# mini_system.net
KiCad netlist of a schematic drawn in Altium Designer
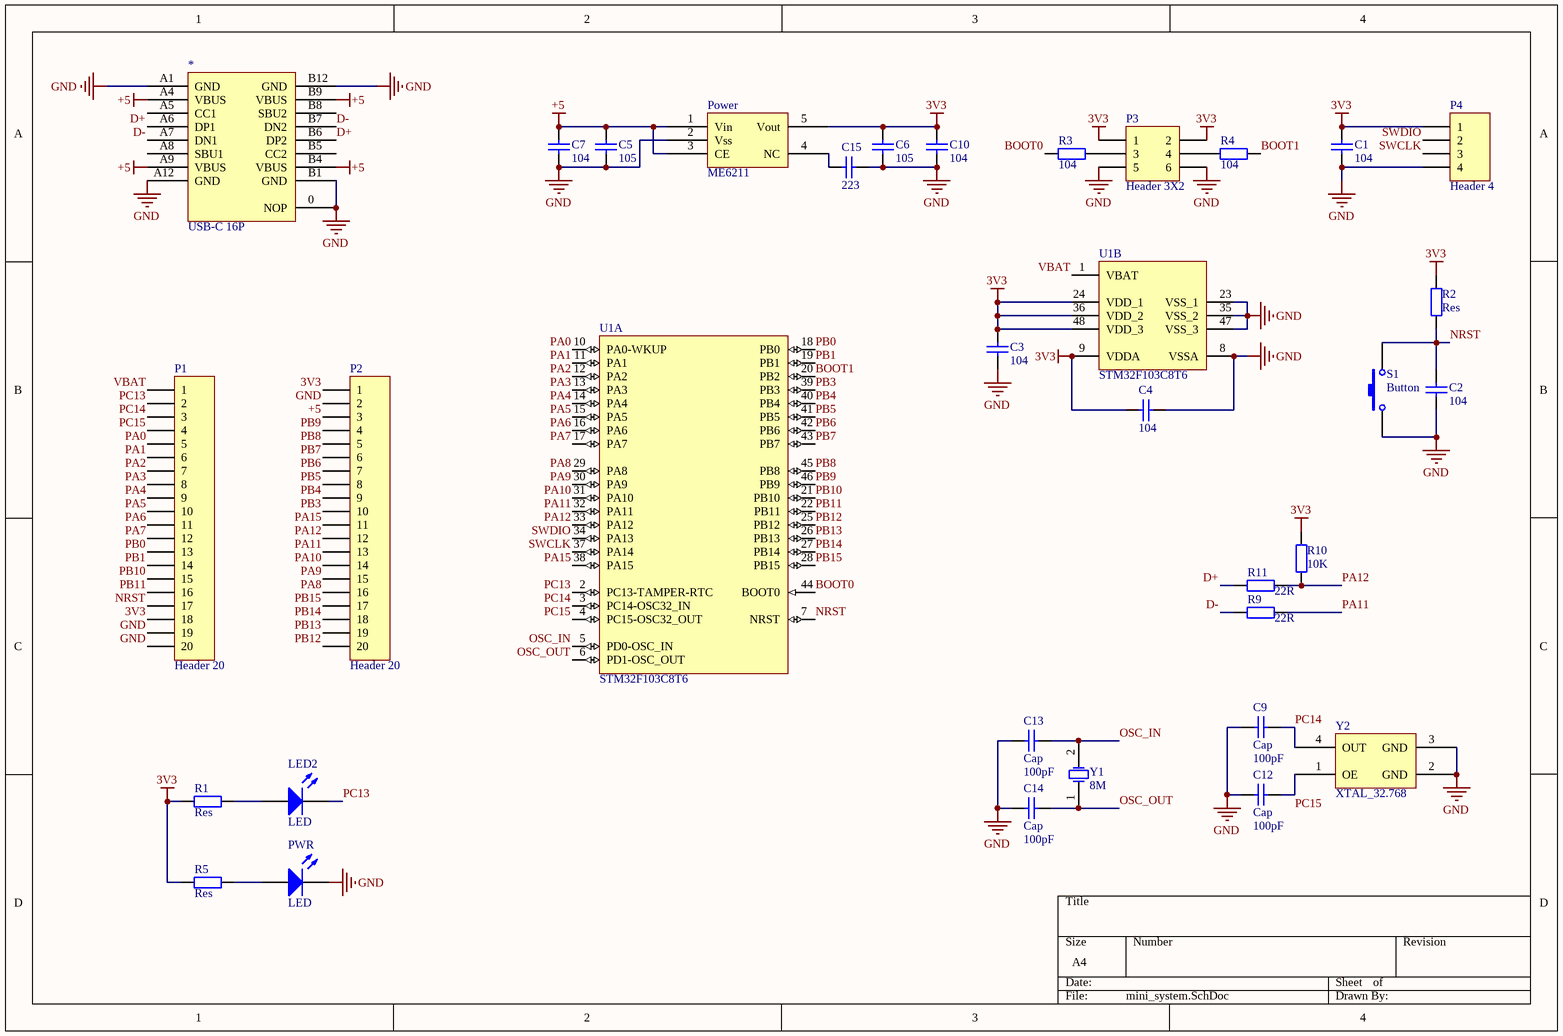
[diagram p0: mini_system.SchDoc]

(export (version "E")
  (design (tool "Eeschema 10.0.6"))
  (components
    (comp (ref "*") (value "USB-C 16P") (footprint "USB-C 16P") (libsource (lib "USB") (part "USB-C 16P")))
    (comp (ref "C1")
      (value "104")
      (footprint "1608[0603]")
      (description "Capacitor")
      (fields (field (name "PUBLISHER") "Altium Limited"))
      (libsource (lib "Miscellaneous Devices") (part "Cap"))
    )
    (comp (ref "C2")
      (value "104")
      (footprint "1608[0603]")
      (description "Capacitor")
      (fields (field (name "PUBLISHER") "Altium Limited"))
      (libsource (lib "Miscellaneous Devices") (part "Cap"))
    )
    (comp (ref "C3")
      (value "104")
      (footprint "1608[0603]")
      (description "Capacitor")
      (fields (field (name "PUBLISHER") "Altium Limited"))
      (libsource (lib "Miscellaneous Devices") (part "Cap"))
    )
    (comp (ref "C4")
      (value "104")
      (footprint "1608[0603]")
      (description "Capacitor")
      (fields (field (name "PUBLISHER") "Altium Limited"))
      (libsource (lib "Miscellaneous Devices") (part "Cap"))
    )
    (comp (ref "C5")
      (value "105")
      (footprint "6-0805_M")
      (description "Capacitor")
      (fields (field (name "PUBLISHER") "Altium Limited"))
      (libsource (lib "Miscellaneous Devices") (part "Cap"))
    )
    (comp (ref "C6")
      (value "105")
      (footprint "6-0805_M")
      (description "Capacitor")
      (fields (field (name "PUBLISHER") "Altium Limited"))
      (libsource (lib "Miscellaneous Devices") (part "Cap"))
    )
    (comp (ref "C7")
      (value "104")
      (footprint "1608[0603]")
      (description "Capacitor")
      (fields (field (name "PUBLISHER") "Altium Limited"))
      (libsource (lib "Miscellaneous Devices") (part "Cap"))
    )
    (comp (ref "C9")
      (value "Cap")
      (footprint "1608[0603]")
      (description "Capacitor")
      (fields (field (name "ALTIUM_VALUE") "100pF") (field (name "PUBLISHER") "Altium Limited"))
      (libsource (lib "Miscellaneous Devices") (part "Cap"))
    )
    (comp (ref "C10")
      (value "104")
      (footprint "1608[0603]")
      (description "Capacitor")
      (fields (field (name "PUBLISHER") "Altium Limited"))
      (libsource (lib "Miscellaneous Devices") (part "Cap"))
    )
    (comp (ref "C12")
      (value "Cap")
      (footprint "1608[0603]")
      (description "Capacitor")
      (fields (field (name "ALTIUM_VALUE") "100pF") (field (name "PUBLISHER") "Altium Limited"))
      (libsource (lib "Miscellaneous Devices") (part "Cap"))
    )
    (comp (ref "C13")
      (value "Cap")
      (footprint "1608[0603]")
      (description "Capacitor")
      (fields (field (name "ALTIUM_VALUE") "100pF") (field (name "PUBLISHER") "Altium Limited"))
      (libsource (lib "Miscellaneous Devices") (part "Cap"))
    )
    (comp (ref "C14")
      (value "Cap")
      (footprint "1608[0603]")
      (description "Capacitor")
      (fields (field (name "ALTIUM_VALUE") "100pF") (field (name "PUBLISHER") "Altium Limited"))
      (libsource (lib "Miscellaneous Devices") (part "Cap"))
    )
    (comp (ref "C15")
      (value "223")
      (footprint "1608[0603]")
      (description "Capacitor")
      (fields (field (name "PUBLISHER") "Altium Limited"))
      (libsource (lib "Miscellaneous Devices") (part "Cap"))
    )
    (comp (ref "LED2")
      (value "LED")
      (footprint "LED")
      (description "Typical INFRARED GaAs LED")
      (fields (field (name "PUBLISHER") "Altium Limited"))
      (libsource (lib "Miscellaneous Devices") (part "LED"))
    )
    (comp (ref "P1")
      (value "Header 20")
      (footprint "HDR1X20")
      (description "Header, 20-Pin")
      (fields (field (name "PUBLISHER") "Altium Limited"))
      (libsource (lib "Miscellaneous Connectors") (part "Header 20"))
    )
    (comp (ref "P2")
      (value "Header 20")
      (footprint "HDR1X20")
      (description "Header, 20-Pin")
      (fields (field (name "PUBLISHER") "Altium Limited"))
      (libsource (lib "Miscellaneous Connectors") (part "Header 20"))
    )
    (comp (ref "P3")
      (value "Header 3X2")
      (footprint "HDR2X3")
      (description "Header, 3-Pin, Dual row")
      (fields (field (name "PUBLISHER") "Altium Limited"))
      (libsource (lib "Miscellaneous Connectors") (part "Header 3X2"))
    )
    (comp (ref "P4")
      (value "Header 4")
      (footprint "HDR1X4")
      (description "Header, 4-Pin")
      (fields (field (name "PUBLISHER") "Altium Limited"))
      (libsource (lib "Miscellaneous Connectors") (part "Header 4"))
    )
    (comp (ref "Power")
      (value "ME6211")
      (footprint "ME6211")
      (description "SOT23-5")
      (libsource (lib "Common_Modules") (part "ME6211"))
    )
    (comp (ref "PWR")
      (value "LED")
      (footprint "LED")
      (description "Typical INFRARED GaAs LED")
      (fields (field (name "PUBLISHER") "Altium Limited"))
      (libsource (lib "Miscellaneous Devices") (part "LED"))
    )
    (comp (ref "R1")
      (value "Res")
      (footprint "1608[0603]")
      (description "Resistor")
      (fields (field (name "PUBLISHER") "Altium Limited"))
      (libsource (lib "Miscellaneous Devices") (part "Res"))
    )
    (comp (ref "R2")
      (value "Res")
      (footprint "1608[0603]")
      (description "Resistor")
      (fields (field (name "PUBLISHER") "Altium Limited"))
      (libsource (lib "") (part "Res_2"))
    )
    (comp (ref "R3")
      (value "104")
      (footprint "1608[0603]")
      (description "Resistor")
      (fields (field (name "PUBLISHER") "Altium Limited"))
      (libsource (lib "Miscellaneous Devices") (part "Res"))
    )
    (comp (ref "R4")
      (value "104")
      (footprint "1608[0603]")
      (description "Resistor")
      (fields (field (name "PUBLISHER") "Altium Limited"))
      (libsource (lib "Miscellaneous Devices") (part "Res"))
    )
    (comp (ref "R5")
      (value "Res")
      (footprint "1608[0603]")
      (description "Resistor")
      (fields (field (name "PUBLISHER") "Altium Limited"))
      (libsource (lib "Miscellaneous Devices") (part "Res"))
    )
    (comp (ref "R9")
      (value "22R")
      (footprint "1608[0603]")
      (description "Resistor")
      (fields (field (name "PUBLISHER") "Altium Limited"))
      (libsource (lib "Miscellaneous Devices") (part "Res"))
    )
    (comp (ref "R10")
      (value "10K")
      (footprint "1608[0603]")
      (description "Resistor")
      (fields (field (name "PUBLISHER") "Altium Limited"))
      (libsource (lib "") (part "Res_1"))
    )
    (comp (ref "R11")
      (value "22R")
      (footprint "1608[0603]")
      (description "Resistor")
      (fields (field (name "PUBLISHER") "Altium Limited"))
      (libsource (lib "Miscellaneous Devices") (part "Res"))
    )
    (comp (ref "S1")
      (value "Button")
      (footprint "BUTTON")
      (description "Switch")
      (fields (field (name "PUBLISHER") "Altium Limited"))
      (libsource (lib "Miscellaneous Devices") (part "Button"))
    )
    (comp (ref "U1")
      (value "STM32F103C8T6")
      (footprint "STM-LQFP48_N")
      (libsource (lib "STMicroelectronics STM32 F1") (part "STM32F103C8T6"))
    )
    (comp (ref "Y1")
      (value "8M")
      (footprint "XTAL3")
      (description "Crystal Oscillator")
      (fields (field (name "PUBLISHER") "Altium Limited"))
      (libsource (lib "Miscellaneous Devices") (part "XTAL"))
    )
    (comp (ref "Y2")
      (value "XTAL_32.768")
      (footprint "MC-306")
      (description "32.768kHz")
      (fields (field (name "PUBLISHER") "Altium Limited"))
      (libsource (lib "Miscellaneous Devices") (part "XTAL_32.768"))
    )
  )
  (nets
    (net (code "1") (name "+5") (class "Default")
      (node (ref "*") (pin "A4") (pinfunction "VBUS_A4") (pintype "passive"))
      (node (ref "*") (pin "A9") (pinfunction "VBUS_A9") (pintype "passive"))
      (node (ref "*") (pin "B4") (pinfunction "VBUS_B4") (pintype "passive"))
      (node (ref "*") (pin "B9") (pinfunction "VBUS_B9") (pintype "passive"))
      (node (ref "C5") (pin "2") (pinfunction "2_2") (pintype "passive"))
      (node (ref "C7") (pin "2") (pinfunction "2_2") (pintype "passive"))
      (node (ref "P2") (pin "3") (pinfunction "3_3") (pintype "passive"))
      (node (ref "Power") (pin "1") (pinfunction "Vin_1") (pintype "passive"))
      (node (ref "Power") (pin "3") (pinfunction "CE_3") (pintype "passive"))
    )
    (net (code "2") (name "/BOOT0") (class "Default")
      (node (ref "R3") (pin "1") (pinfunction "1_1") (pintype "passive"))
      (node (ref "U1") (pin "44") (pinfunction "BOOT0_44") (pintype "input"))
    )
    (net (code "3") (name "/BOOT1") (class "Default")
      (node (ref "R4") (pin "2") (pinfunction "2_2") (pintype "passive"))
      (node (ref "U1") (pin "20") (pinfunction "PB2_20") (pintype "bidirectional"))
    )
    (net (code "4") (name "/D+") (class "Default")
      (node (ref "*") (pin "A6") (pinfunction "DP1_A6") (pintype "passive"))
      (node (ref "*") (pin "B6") (pinfunction "DP2_B6") (pintype "passive"))
      (node (ref "R11") (pin "1") (pinfunction "1_1") (pintype "passive"))
    )
    (net (code "5") (name "/D-") (class "Default")
      (node (ref "*") (pin "A7") (pinfunction "DN1_A7") (pintype "passive"))
      (node (ref "*") (pin "B7") (pinfunction "DN2_B7") (pintype "passive"))
      (node (ref "R9") (pin "1") (pinfunction "1_1") (pintype "passive"))
    )
    (net (code "6") (name "/NRST") (class "Default")
      (node (ref "C2") (pin "2") (pinfunction "2_2") (pintype "passive"))
      (node (ref "P1") (pin "17") (pinfunction "17_17") (pintype "passive"))
      (node (ref "R2") (pin "1") (pinfunction "1_1") (pintype "passive"))
      (node (ref "S1") (pin "2") (pinfunction "2_2") (pintype "passive"))
      (node (ref "U1") (pin "7") (pinfunction "NRST_7") (pintype "bidirectional"))
    )
    (net (code "7") (name "/OSC_IN") (class "Default")
      (node (ref "C13") (pin "1") (pinfunction "1_1") (pintype "passive"))
      (node (ref "U1") (pin "5") (pinfunction "PD0-OSC_IN_5") (pintype "bidirectional"))
      (node (ref "Y1") (pin "2") (pinfunction "OSC2_2") (pintype "passive"))
    )
    (net (code "8") (name "/OSC_OUT") (class "Default")
      (node (ref "C14") (pin "2") (pinfunction "2_2") (pintype "passive"))
      (node (ref "U1") (pin "6") (pinfunction "PD1-OSC_OUT_6") (pintype "bidirectional"))
      (node (ref "Y1") (pin "1") (pinfunction "OSC1_1") (pintype "passive"))
    )
    (net (code "9") (name "/PA0") (class "Default")
      (node (ref "P1") (pin "5") (pinfunction "5_5") (pintype "passive"))
      (node (ref "U1") (pin "10") (pinfunction "PA0-WKUP_10") (pintype "bidirectional"))
    )
    (net (code "10") (name "/PA1") (class "Default")
      (node (ref "P1") (pin "6") (pinfunction "6_6") (pintype "passive"))
      (node (ref "U1") (pin "11") (pinfunction "PA1_11") (pintype "bidirectional"))
    )
    (net (code "11") (name "/PA2") (class "Default")
      (node (ref "P1") (pin "7") (pinfunction "7_7") (pintype "passive"))
      (node (ref "U1") (pin "12") (pinfunction "PA2_12") (pintype "bidirectional"))
    )
    (net (code "12") (name "/PA3") (class "Default")
      (node (ref "P1") (pin "8") (pinfunction "8_8") (pintype "passive"))
      (node (ref "U1") (pin "13") (pinfunction "PA3_13") (pintype "bidirectional"))
    )
    (net (code "13") (name "/PA4") (class "Default")
      (node (ref "P1") (pin "9") (pinfunction "9_9") (pintype "passive"))
      (node (ref "U1") (pin "14") (pinfunction "PA4_14") (pintype "bidirectional"))
    )
    (net (code "14") (name "/PA5") (class "Default")
      (node (ref "P1") (pin "10") (pinfunction "10_10") (pintype "passive"))
      (node (ref "U1") (pin "15") (pinfunction "PA5_15") (pintype "bidirectional"))
    )
    (net (code "15") (name "/PA6") (class "Default")
      (node (ref "P1") (pin "11") (pinfunction "11_11") (pintype "passive"))
      (node (ref "U1") (pin "16") (pinfunction "PA6_16") (pintype "bidirectional"))
    )
    (net (code "16") (name "/PA7") (class "Default")
      (node (ref "P1") (pin "12") (pinfunction "12_12") (pintype "passive"))
      (node (ref "U1") (pin "17") (pinfunction "PA7_17") (pintype "bidirectional"))
    )
    (net (code "17") (name "/PA8") (class "Default")
      (node (ref "P2") (pin "16") (pinfunction "16_16") (pintype "passive"))
      (node (ref "U1") (pin "29") (pinfunction "PA8_29") (pintype "bidirectional"))
    )
    (net (code "18") (name "/PA9") (class "Default")
      (node (ref "P2") (pin "15") (pinfunction "15_15") (pintype "passive"))
      (node (ref "U1") (pin "30") (pinfunction "PA9_30") (pintype "bidirectional"))
    )
    (net (code "19") (name "/PA10") (class "Default")
      (node (ref "P2") (pin "14") (pinfunction "14_14") (pintype "passive"))
      (node (ref "U1") (pin "31") (pinfunction "PA10_31") (pintype "bidirectional"))
    )
    (net (code "20") (name "/PA11") (class "Default")
      (node (ref "P2") (pin "13") (pinfunction "13_13") (pintype "passive"))
      (node (ref "R9") (pin "2") (pinfunction "2_2") (pintype "passive"))
      (node (ref "U1") (pin "32") (pinfunction "PA11_32") (pintype "bidirectional"))
    )
    (net (code "21") (name "/PA12") (class "Default")
      (node (ref "P2") (pin "12") (pinfunction "12_12") (pintype "passive"))
      (node (ref "R10") (pin "2") (pinfunction "2_2") (pintype "passive"))
      (node (ref "R11") (pin "2") (pinfunction "2_2") (pintype "passive"))
      (node (ref "U1") (pin "33") (pinfunction "PA12_33") (pintype "bidirectional"))
    )
    (net (code "22") (name "/PA15") (class "Default")
      (node (ref "P2") (pin "11") (pinfunction "11_11") (pintype "passive"))
      (node (ref "U1") (pin "38") (pinfunction "PA15_38") (pintype "bidirectional"))
    )
    (net (code "23") (name "/PB0") (class "Default")
      (node (ref "P1") (pin "13") (pinfunction "13_13") (pintype "passive"))
      (node (ref "U1") (pin "18") (pinfunction "PB0_18") (pintype "bidirectional"))
    )
    (net (code "24") (name "/PB1") (class "Default")
      (node (ref "P1") (pin "14") (pinfunction "14_14") (pintype "passive"))
      (node (ref "U1") (pin "19") (pinfunction "PB1_19") (pintype "bidirectional"))
    )
    (net (code "25") (name "/PB3") (class "Default")
      (node (ref "P2") (pin "10") (pinfunction "10_10") (pintype "passive"))
      (node (ref "U1") (pin "39") (pinfunction "PB3_39") (pintype "bidirectional"))
    )
    (net (code "26") (name "/PB4") (class "Default")
      (node (ref "P2") (pin "9") (pinfunction "9_9") (pintype "passive"))
      (node (ref "U1") (pin "40") (pinfunction "PB4_40") (pintype "bidirectional"))
    )
    (net (code "27") (name "/PB5") (class "Default")
      (node (ref "P2") (pin "8") (pinfunction "8_8") (pintype "passive"))
      (node (ref "U1") (pin "41") (pinfunction "PB5_41") (pintype "bidirectional"))
    )
    (net (code "28") (name "/PB6") (class "Default")
      (node (ref "P2") (pin "7") (pinfunction "7_7") (pintype "passive"))
      (node (ref "U1") (pin "42") (pinfunction "PB6_42") (pintype "bidirectional"))
    )
    (net (code "29") (name "/PB7") (class "Default")
      (node (ref "P2") (pin "6") (pinfunction "6_6") (pintype "passive"))
      (node (ref "U1") (pin "43") (pinfunction "PB7_43") (pintype "bidirectional"))
    )
    (net (code "30") (name "/PB8") (class "Default")
      (node (ref "P2") (pin "5") (pinfunction "5_5") (pintype "passive"))
      (node (ref "U1") (pin "45") (pinfunction "PB8_45") (pintype "bidirectional"))
    )
    (net (code "31") (name "/PB9") (class "Default")
      (node (ref "P2") (pin "4") (pinfunction "4_4") (pintype "passive"))
      (node (ref "U1") (pin "46") (pinfunction "PB9_46") (pintype "bidirectional"))
    )
    (net (code "32") (name "/PB10") (class "Default")
      (node (ref "P1") (pin "15") (pinfunction "15_15") (pintype "passive"))
      (node (ref "U1") (pin "21") (pinfunction "PB10_21") (pintype "bidirectional"))
    )
    (net (code "33") (name "/PB11") (class "Default")
      (node (ref "P1") (pin "16") (pinfunction "16_16") (pintype "passive"))
      (node (ref "U1") (pin "22") (pinfunction "PB11_22") (pintype "bidirectional"))
    )
    (net (code "34") (name "/PB12") (class "Default")
      (node (ref "P2") (pin "20") (pinfunction "20_20") (pintype "passive"))
      (node (ref "U1") (pin "25") (pinfunction "PB12_25") (pintype "bidirectional"))
    )
    (net (code "35") (name "/PB13") (class "Default")
      (node (ref "P2") (pin "19") (pinfunction "19_19") (pintype "passive"))
      (node (ref "U1") (pin "26") (pinfunction "PB13_26") (pintype "bidirectional"))
    )
    (net (code "36") (name "/PB14") (class "Default")
      (node (ref "P2") (pin "18") (pinfunction "18_18") (pintype "passive"))
      (node (ref "U1") (pin "27") (pinfunction "PB14_27") (pintype "bidirectional"))
    )
    (net (code "37") (name "/PB15") (class "Default")
      (node (ref "P2") (pin "17") (pinfunction "17_17") (pintype "passive"))
      (node (ref "U1") (pin "28") (pinfunction "PB15_28") (pintype "bidirectional"))
    )
    (net (code "38") (name "/PC13") (class "Default")
      (node (ref "LED2") (pin "2") (pinfunction "K_2") (pintype "passive"))
      (node (ref "P1") (pin "2") (pinfunction "2_2") (pintype "passive"))
      (node (ref "U1") (pin "2") (pinfunction "PC13-TAMPER-RTC_2") (pintype "bidirectional"))
    )
    (net (code "39") (name "/PC14") (class "Default")
      (node (ref "C9") (pin "1") (pinfunction "1_1") (pintype "passive"))
      (node (ref "P1") (pin "3") (pinfunction "3_3") (pintype "passive"))
      (node (ref "U1") (pin "3") (pinfunction "PC14-OSC32_IN_3") (pintype "bidirectional"))
      (node (ref "Y2") (pin "4") (pinfunction "OUT_4") (pintype "passive"))
    )
    (net (code "40") (name "/PC15") (class "Default")
      (node (ref "C12") (pin "2") (pinfunction "2_2") (pintype "passive"))
      (node (ref "P1") (pin "4") (pinfunction "4_4") (pintype "passive"))
      (node (ref "U1") (pin "4") (pinfunction "PC15-OSC32_OUT_4") (pintype "bidirectional"))
      (node (ref "Y2") (pin "1") (pinfunction "OE_1") (pintype "passive"))
    )
    (net (code "41") (name "/SWCLK") (class "Default")
      (node (ref "P4") (pin "3") (pinfunction "3_3") (pintype "passive"))
      (node (ref "U1") (pin "37") (pinfunction "PA14_37") (pintype "bidirectional"))
    )
    (net (code "42") (name "/SWDIO") (class "Default")
      (node (ref "P4") (pin "2") (pinfunction "2_2") (pintype "passive"))
      (node (ref "U1") (pin "34") (pinfunction "PA13_34") (pintype "bidirectional"))
    )
    (net (code "43") (name "/VBAT") (class "Default")
      (node (ref "P1") (pin "1") (pinfunction "1_1") (pintype "passive"))
      (node (ref "U1") (pin "1") (pinfunction "VBAT_1") (pintype "power_in"))
    )
    (net (code "44") (name "3V3") (class "Default")
      (node (ref "C1") (pin "2") (pinfunction "2_2") (pintype "passive"))
      (node (ref "C10") (pin "2") (pinfunction "2_2") (pintype "passive"))
      (node (ref "C3") (pin "2") (pinfunction "2_2") (pintype "passive"))
      (node (ref "C4") (pin "2") (pinfunction "2_2") (pintype "passive"))
      (node (ref "C6") (pin "2") (pinfunction "2_2") (pintype "passive"))
      (node (ref "P1") (pin "18") (pinfunction "18_18") (pintype "passive"))
      (node (ref "P2") (pin "1") (pinfunction "1_1") (pintype "passive"))
      (node (ref "P3") (pin "1") (pinfunction "1_1") (pintype "passive"))
      (node (ref "P3") (pin "2") (pinfunction "2_2") (pintype "passive"))
      (node (ref "P4") (pin "1") (pinfunction "1_1") (pintype "passive"))
      (node (ref "Power") (pin "5") (pinfunction "Vout_5") (pintype "passive"))
      (node (ref "R1") (pin "1") (pinfunction "1_1") (pintype "passive"))
      (node (ref "R10") (pin "1") (pinfunction "1_1") (pintype "passive"))
      (node (ref "R2") (pin "2") (pinfunction "2_2") (pintype "passive"))
      (node (ref "R5") (pin "1") (pinfunction "1_1") (pintype "passive"))
      (node (ref "U1") (pin "24") (pinfunction "VDD_1_24") (pintype "power_in"))
      (node (ref "U1") (pin "36") (pinfunction "VDD_2_36") (pintype "power_in"))
      (node (ref "U1") (pin "48") (pinfunction "VDD_3_48") (pintype "power_in"))
      (node (ref "U1") (pin "9") (pinfunction "VDDA_9") (pintype "power_in"))
    )
    (net (code "45") (name "GND") (class "Default")
      (node (ref "*") (pin "0") (pinfunction "NOP_0") (pintype "passive"))
      (node (ref "*") (pin "A1") (pinfunction "GND_A1") (pintype "passive"))
      (node (ref "*") (pin "A12") (pinfunction "GND_A12") (pintype "passive"))
      (node (ref "*") (pin "B1") (pinfunction "GND_B1") (pintype "passive"))
      (node (ref "*") (pin "B12") (pinfunction "GND_B12") (pintype "passive"))
      (node (ref "C1") (pin "1") (pinfunction "1_1") (pintype "passive"))
      (node (ref "C10") (pin "1") (pinfunction "1_1") (pintype "passive"))
      (node (ref "C12") (pin "1") (pinfunction "1_1") (pintype "passive"))
      (node (ref "C13") (pin "2") (pinfunction "2_2") (pintype "passive"))
      (node (ref "C14") (pin "1") (pinfunction "1_1") (pintype "passive"))
      (node (ref "C15") (pin "2") (pinfunction "2_2") (pintype "passive"))
      (node (ref "C2") (pin "1") (pinfunction "1_1") (pintype "passive"))
      (node (ref "C3") (pin "1") (pinfunction "1_1") (pintype "passive"))
      (node (ref "C4") (pin "1") (pinfunction "1_1") (pintype "passive"))
      (node (ref "C5") (pin "1") (pinfunction "1_1") (pintype "passive"))
      (node (ref "C6") (pin "1") (pinfunction "1_1") (pintype "passive"))
      (node (ref "C7") (pin "1") (pinfunction "1_1") (pintype "passive"))
      (node (ref "C9") (pin "2") (pinfunction "2_2") (pintype "passive"))
      (node (ref "P1") (pin "19") (pinfunction "19_19") (pintype "passive"))
      (node (ref "P1") (pin "20") (pinfunction "20_20") (pintype "passive"))
      (node (ref "P2") (pin "2") (pinfunction "2_2") (pintype "passive"))
      (node (ref "P3") (pin "5") (pinfunction "5_5") (pintype "passive"))
      (node (ref "P3") (pin "6") (pinfunction "6_6") (pintype "passive"))
      (node (ref "P4") (pin "4") (pinfunction "4_4") (pintype "passive"))
      (node (ref "PWR") (pin "2") (pinfunction "K_2") (pintype "passive"))
      (node (ref "Power") (pin "2") (pinfunction "Vss_2") (pintype "passive"))
      (node (ref "S1") (pin "1") (pinfunction "1_1") (pintype "passive"))
      (node (ref "U1") (pin "23") (pinfunction "VSS_1_23") (pintype "power_in"))
      (node (ref "U1") (pin "35") (pinfunction "VSS_2_35") (pintype "power_in"))
      (node (ref "U1") (pin "47") (pinfunction "VSS_3_47") (pintype "power_in"))
      (node (ref "U1") (pin "8") (pinfunction "VSSA_8") (pintype "power_in"))
      (node (ref "Y2") (pin "2") (pinfunction "GND_2") (pintype "passive"))
      (node (ref "Y2") (pin "3") (pinfunction "GND_3") (pintype "passive"))
    )
    (net (code "46") (name "Net-(LED2-A)") (class "Default")
      (node (ref "LED2") (pin "1") (pinfunction "A_1") (pintype "passive"))
      (node (ref "R1") (pin "2") (pinfunction "2_2") (pintype "passive"))
    )
    (net (code "47") (name "Net-(P3-Pad3)") (class "Default")
      (node (ref "P3") (pin "3") (pinfunction "3_3") (pintype "passive"))
      (node (ref "R3") (pin "2") (pinfunction "2_2") (pintype "passive"))
    )
    (net (code "48") (name "Net-(P3-Pad4)") (class "Default")
      (node (ref "P3") (pin "4") (pinfunction "4_4") (pintype "passive"))
      (node (ref "R4") (pin "1") (pinfunction "1_1") (pintype "passive"))
    )
    (net (code "49") (name "Net-(PWR-A)") (class "Default")
      (node (ref "PWR") (pin "1") (pinfunction "A_1") (pintype "passive"))
      (node (ref "R5") (pin "2") (pinfunction "2_2") (pintype "passive"))
    )
    (net (code "50") (name "Net-(Power-NC)") (class "Default")
      (node (ref "C15") (pin "1") (pinfunction "1_1") (pintype "passive"))
      (node (ref "Power") (pin "4") (pinfunction "NC_4") (pintype "passive"))
    )
    (net (code "51") (name "unconnected-(*-CC1-PadA5)") (class "Default")
      (node (ref "*") (pin "A5") (pinfunction "CC1_A5") (pintype "passive"))
    )
    (net (code "52") (name "unconnected-(*-CC2-PadB5)") (class "Default")
      (node (ref "*") (pin "B5") (pinfunction "CC2_B5") (pintype "passive"))
    )
    (net (code "53") (name "unconnected-(*-SBU1-PadA8)") (class "Default")
      (node (ref "*") (pin "A8") (pinfunction "SBU1_A8") (pintype "passive"))
    )
    (net (code "54") (name "unconnected-(*-SBU2-PadB8)") (class "Default")
      (node (ref "*") (pin "B8") (pinfunction "SBU2_B8") (pintype "passive"))
    )
  )
)
